# Board.net
KiCad netlist of a schematic drawn in EAGLE
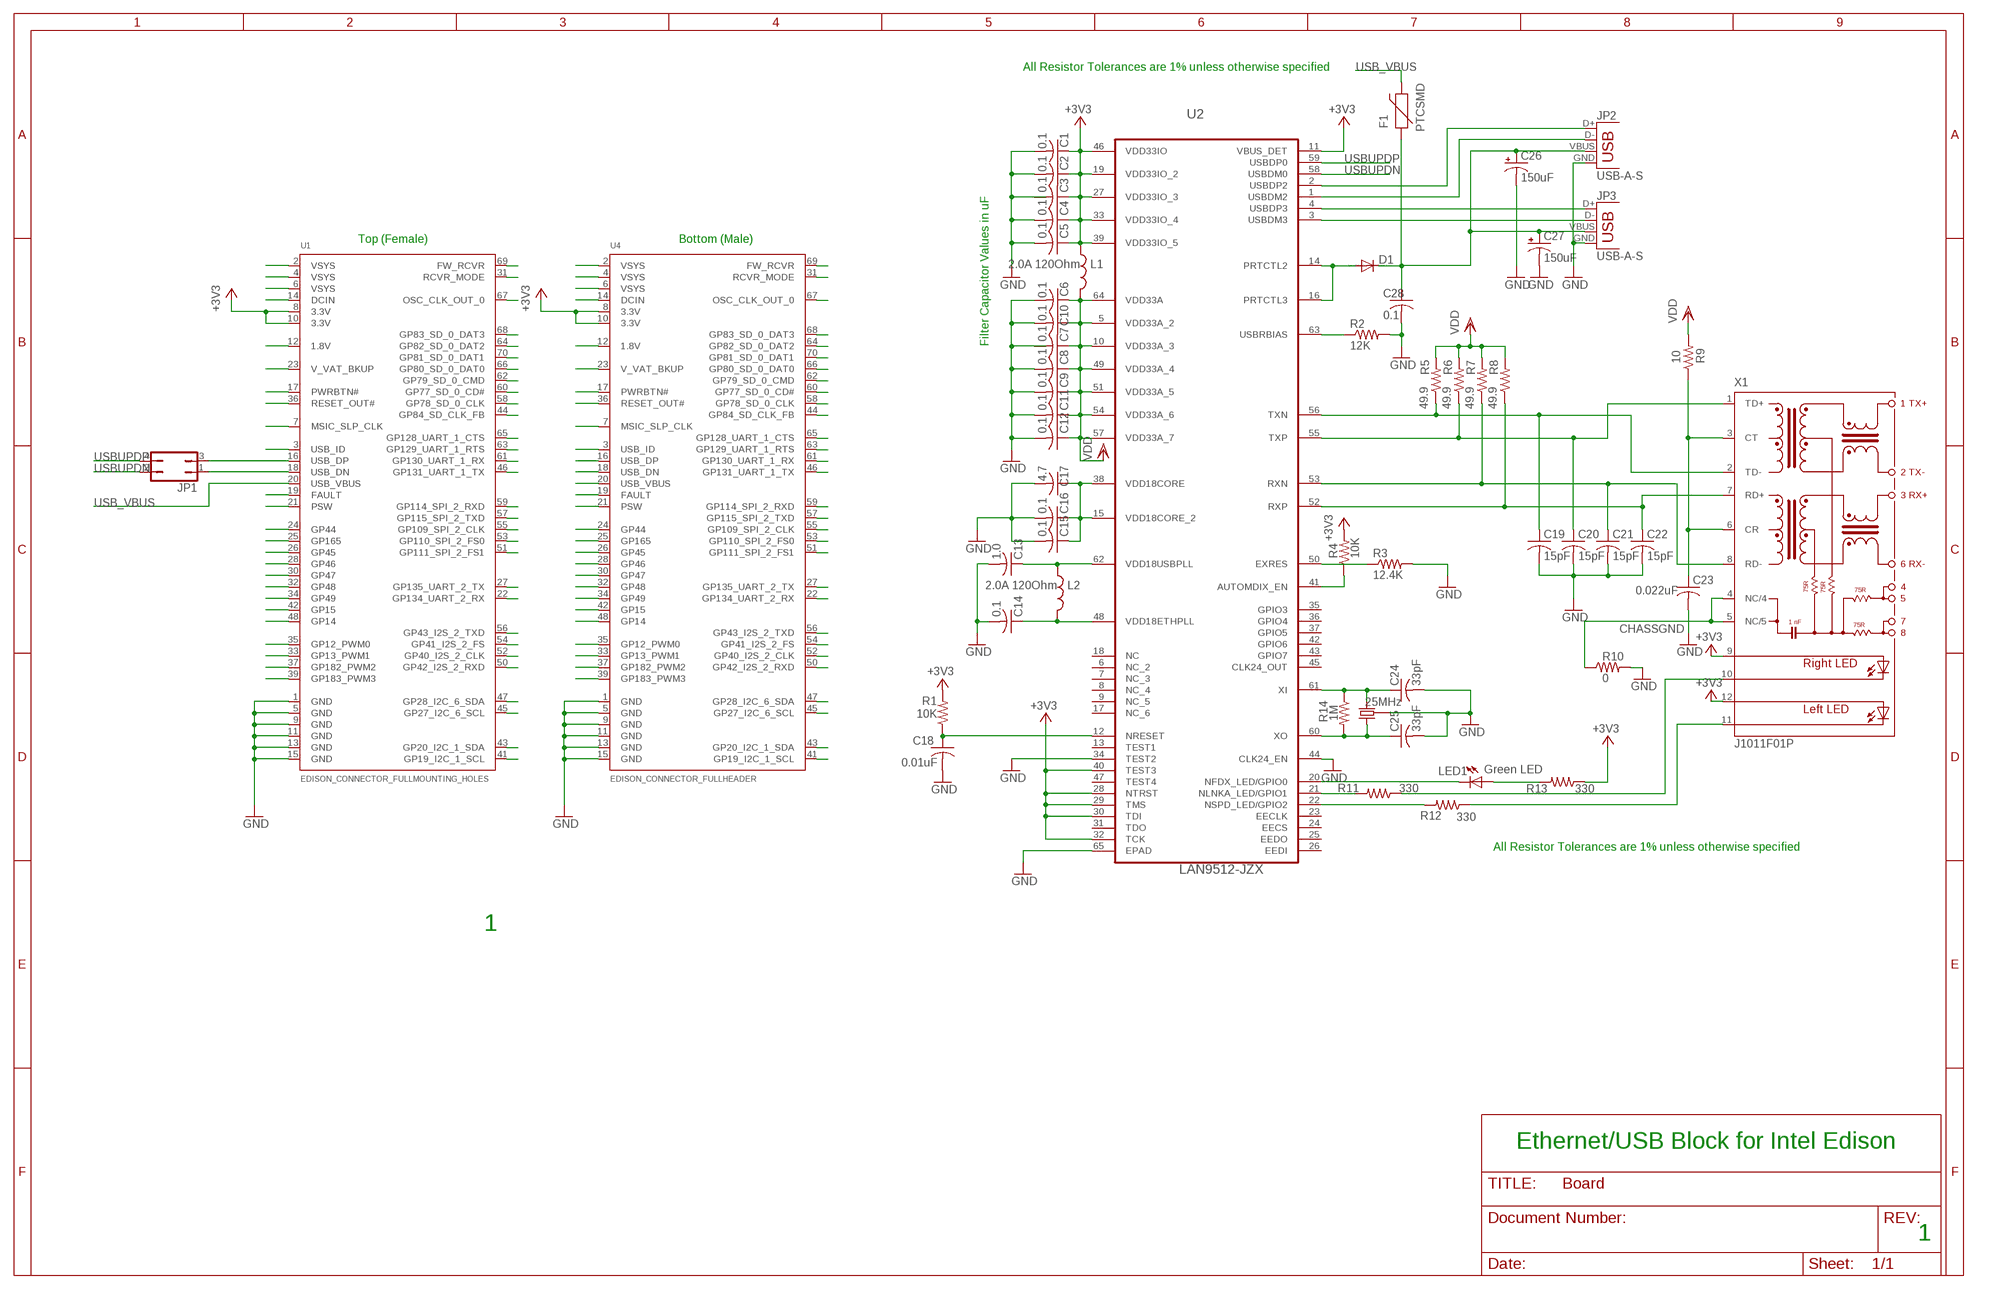
[diagram p0: schematic, sheet 1]

(export (version "E")
  (design (tool "Eeschema 10.0.6"))
  (components
    (comp (ref "C1")
      (value "0.1")
      (footprint "eagle-import:C0402K")
      (libsource (lib "eagle-import") (part "C-USC0402K"))
    )
    (comp (ref "C2")
      (value "0.1")
      (footprint "eagle-import:C0402K")
      (libsource (lib "eagle-import") (part "C-USC0402K"))
    )
    (comp (ref "C3")
      (value "0.1")
      (footprint "eagle-import:C0402K")
      (libsource (lib "eagle-import") (part "C-USC0402K"))
    )
    (comp (ref "C4")
      (value "0.1")
      (footprint "eagle-import:C0402K")
      (libsource (lib "eagle-import") (part "C-USC0402K"))
    )
    (comp (ref "C5")
      (value "0.1")
      (footprint "eagle-import:C0402K")
      (libsource (lib "eagle-import") (part "C-USC0402K"))
    )
    (comp (ref "C6")
      (value "0.1")
      (footprint "eagle-import:C0402K")
      (libsource (lib "eagle-import") (part "C-USC0402K"))
    )
    (comp (ref "C7")
      (value "0.1")
      (footprint "eagle-import:C0402K")
      (libsource (lib "eagle-import") (part "C-USC0402K"))
    )
    (comp (ref "C8")
      (value "0.1")
      (footprint "eagle-import:C0402K")
      (libsource (lib "eagle-import") (part "C-USC0402K"))
    )
    (comp (ref "C9")
      (value "0.1")
      (footprint "eagle-import:C0402K")
      (libsource (lib "eagle-import") (part "C-USC0402K"))
    )
    (comp (ref "C10")
      (value "0.1")
      (footprint "eagle-import:C0402K")
      (libsource (lib "eagle-import") (part "C-USC0402K"))
    )
    (comp (ref "C11")
      (value "0.1")
      (footprint "eagle-import:C0402K")
      (libsource (lib "eagle-import") (part "C-USC0402K"))
    )
    (comp (ref "C12")
      (value "0.1")
      (footprint "eagle-import:C0402K")
      (libsource (lib "eagle-import") (part "C-USC0402K"))
    )
    (comp (ref "C13")
      (value "1.0")
      (footprint "eagle-import:C0402K")
      (libsource (lib "eagle-import") (part "C-USC0402K"))
    )
    (comp (ref "C14")
      (value "0.1")
      (footprint "eagle-import:C0402K")
      (libsource (lib "eagle-import") (part "C-USC0402K"))
    )
    (comp (ref "C15")
      (value "0.1")
      (footprint "eagle-import:C0402K")
      (libsource (lib "eagle-import") (part "C-USC0402K"))
    )
    (comp (ref "C16")
      (value "0.1")
      (footprint "eagle-import:C0402K")
      (libsource (lib "eagle-import") (part "C-USC0402K"))
    )
    (comp (ref "C17")
      (value "4.7")
      (footprint "eagle-import:C0603K")
      (libsource (lib "eagle-import") (part "C-USC0603K"))
    )
    (comp (ref "C18")
      (value "0.01uF")
      (footprint "eagle-import:C0603K")
      (libsource (lib "eagle-import") (part "C-USC0603K"))
    )
    (comp (ref "C19")
      (value "15pF")
      (footprint "eagle-import:C0402")
      (libsource (lib "eagle-import") (part "C-USC0402"))
    )
    (comp (ref "C20")
      (value "15pF")
      (footprint "eagle-import:C0402")
      (libsource (lib "eagle-import") (part "C-USC0402"))
    )
    (comp (ref "C21")
      (value "15pF")
      (footprint "eagle-import:C0402")
      (libsource (lib "eagle-import") (part "C-USC0402"))
    )
    (comp (ref "C22")
      (value "15pF")
      (footprint "eagle-import:C0402")
      (libsource (lib "eagle-import") (part "C-USC0402"))
    )
    (comp (ref "C23")
      (value "0.022uF")
      (footprint "eagle-import:C0805")
      (libsource (lib "eagle-import") (part "resistor_C-USC0805"))
    )
    (comp (ref "C24")
      (value "33pF")
      (footprint "eagle-import:C0402")
      (libsource (lib "eagle-import") (part "C-USC0402"))
    )
    (comp (ref "C25")
      (value "33pF")
      (footprint "eagle-import:C0402")
      (libsource (lib "eagle-import") (part "C-USC0402"))
    )
    (comp (ref "C26")
      (value "150uF")
      (footprint "eagle-import:PANASONIC_E")
      (libsource (lib "eagle-import") (part "CAP_POLE"))
    )
    (comp (ref "C27")
      (value "150uF")
      (footprint "eagle-import:PANASONIC_E")
      (libsource (lib "eagle-import") (part "CAP_POLE"))
    )
    (comp (ref "C28")
      (value "0.1")
      (footprint "eagle-import:C0402K")
      (libsource (lib "eagle-import") (part "C-USC0402K"))
    )
    (comp (ref "D1")
      (value "DIODE-SOD123")
      (footprint "eagle-import:SOD123")
      (libsource (lib "eagle-import") (part "DIODE-SOD123"))
    )
    (comp (ref "F1")
      (value "PTCSMD")
      (footprint "eagle-import:PTC-1206")
      (libsource (lib "eagle-import") (part "PTCSMD"))
    )
    (comp (ref "JP1")
      (value "JP2Q")
      (footprint "eagle-import:JP2Q")
      (libsource (lib "eagle-import") (part "JP2Q"))
    )
    (comp (ref "JP2")
      (value "USB-A-S")
      (footprint "eagle-import:USB-A-S")
      (libsource (lib "eagle-import") (part "USB-A-S"))
    )
    (comp (ref "JP3")
      (value "USB-A-S")
      (footprint "eagle-import:USB-A-S")
      (libsource (lib "eagle-import") (part "USB-A-S"))
    )
    (comp (ref "L1")
      (value "2.0A 120Ohm")
      (footprint "eagle-import:L0603")
      (libsource (lib "eagle-import") (part "L-US0603"))
    )
    (comp (ref "L2")
      (value "2.0A 120Ohm")
      (footprint "eagle-import:L0603")
      (libsource (lib "eagle-import") (part "L-US0603"))
    )
    (comp (ref "LED1")
      (value "Green LED")
      (footprint "eagle-import:CHIPLED_0603")
      (libsource (lib "eagle-import") (part "LEDCHIPLED_0603"))
    )
    (comp (ref "R1")
      (value "10K")
      (footprint "eagle-import:R0603")
      (libsource (lib "eagle-import") (part "R-US_R0603"))
    )
    (comp (ref "R2")
      (value "12K")
      (footprint "eagle-import:R0603")
      (libsource (lib "eagle-import") (part "R-US_R0603"))
    )
    (comp (ref "R3")
      (value "12.4K")
      (footprint "eagle-import:R0603")
      (libsource (lib "eagle-import") (part "R-US_R0603"))
    )
    (comp (ref "R4")
      (value "10K")
      (footprint "eagle-import:R0603")
      (libsource (lib "eagle-import") (part "R-US_R0603"))
    )
    (comp (ref "R5")
      (value "49.9")
      (footprint "eagle-import:R0402")
      (libsource (lib "eagle-import") (part "R-US_R0402"))
    )
    (comp (ref "R6")
      (value "49.9")
      (footprint "eagle-import:R0402")
      (libsource (lib "eagle-import") (part "R-US_R0402"))
    )
    (comp (ref "R7")
      (value "49.9")
      (footprint "eagle-import:R0402")
      (libsource (lib "eagle-import") (part "R-US_R0402"))
    )
    (comp (ref "R8")
      (value "49.9")
      (footprint "eagle-import:R0402")
      (libsource (lib "eagle-import") (part "R-US_R0402"))
    )
    (comp (ref "R9")
      (value "10")
      (footprint "eagle-import:R0402")
      (libsource (lib "eagle-import") (part "R-US_R0402"))
    )
    (comp (ref "R10")
      (value "0")
      (footprint "eagle-import:R1210")
      (libsource (lib "eagle-import") (part "R-US_R1210"))
    )
    (comp (ref "R11")
      (value "330")
      (footprint "eagle-import:R0402")
      (libsource (lib "eagle-import") (part "R-US_R0402"))
    )
    (comp (ref "R12")
      (value "330")
      (footprint "eagle-import:R0402")
      (libsource (lib "eagle-import") (part "R-US_R0402"))
    )
    (comp (ref "R13")
      (value "330")
      (footprint "eagle-import:R0402")
      (libsource (lib "eagle-import") (part "R-US_R0402"))
    )
    (comp (ref "R14")
      (value "1M")
      (footprint "eagle-import:R0402")
      (libsource (lib "eagle-import") (part "R-US_R0402"))
    )
    (comp (ref "U$1")
      (value "25MHz")
      (footprint "eagle-import:CRYSTAL-SMD-5X3")
      (libsource (lib "eagle-import") (part "CRYSTAL-GROUNDED"))
    )
    (comp (ref "U1")
      (value "EDISON_CONNECTOR_FULLMOUNTING_HOLES")
      (footprint "eagle-import:EDISON_DAUGHTER")
      (libsource (lib "eagle-import") (part "EDISON_CONNECTOR_FULLMOUNTING_HOLES"))
    )
    (comp (ref "U2")
      (value "LAN9512-JZX")
      (footprint "eagle-import:QFN50P900X900X100-65N")
      (libsource (lib "eagle-import") (part "LAN9512-JZX"))
    )
    (comp (ref "U4")
      (value "EDISON_CONNECTOR_FULLHEADER")
      (footprint "eagle-import:DF40C-70DP-0.4(51)")
      (libsource (lib "eagle-import") (part "EDISON_CONNECTOR_FULLHEADER"))
    )
    (comp (ref "X1")
      (value "J1011F01P")
      (footprint "eagle-import:J1")
      (libsource (lib "eagle-import") (part "J1011F01P"))
    )
  )
  (nets
    (net (code "1") (name "+3V3") (class "Default")
      (node (ref "C1") (pin "1") (pinfunction "1_1") (pintype "passive"))
      (node (ref "C2") (pin "1") (pinfunction "1_1") (pintype "passive"))
      (node (ref "C3") (pin "1") (pinfunction "1_1") (pintype "passive"))
      (node (ref "C4") (pin "1") (pinfunction "1_1") (pintype "passive"))
      (node (ref "C5") (pin "1") (pinfunction "1_1") (pintype "passive"))
      (node (ref "L1") (pin "1") (pinfunction "1_1") (pintype "passive"))
      (node (ref "R1") (pin "2") (pinfunction "2_2") (pintype "passive"))
      (node (ref "R13") (pin "1") (pinfunction "1_1") (pintype "passive"))
      (node (ref "R4") (pin "2") (pinfunction "2_2") (pintype "passive"))
      (node (ref "U1") (pin "10") (pinfunction "3.3V_10") (pintype "bidirectional"))
      (node (ref "U1") (pin "8") (pinfunction "3.3V_8") (pintype "bidirectional"))
      (node (ref "U2") (pin "11") (pinfunction "VBUS_DET_11") (pintype "power_in"))
      (node (ref "U2") (pin "19") (pinfunction "VDD33IO_2_19") (pintype "power_in"))
      (node (ref "U2") (pin "27") (pinfunction "VDD33IO_3_27") (pintype "power_in"))
      (node (ref "U2") (pin "28") (pinfunction "NTRST_28") (pintype "passive"))
      (node (ref "U2") (pin "29") (pinfunction "TMS_29") (pintype "passive"))
      (node (ref "U2") (pin "30") (pinfunction "TDI_30") (pintype "passive"))
      (node (ref "U2") (pin "32") (pinfunction "TCK_32") (pintype "passive"))
      (node (ref "U2") (pin "33") (pinfunction "VDD33IO_4_33") (pintype "power_in"))
      (node (ref "U2") (pin "39") (pinfunction "VDD33IO_5_39") (pintype "power_in"))
      (node (ref "U2") (pin "40") (pinfunction "TEST3_40") (pintype "passive"))
      (node (ref "U2") (pin "46") (pinfunction "VDD33IO_46") (pintype "power_in"))
      (node (ref "U4") (pin "10") (pinfunction "3.3V_10") (pintype "bidirectional"))
      (node (ref "U4") (pin "8") (pinfunction "3.3V_8") (pintype "bidirectional"))
      (node (ref "X1") (pin "12") (pinfunction "AL_12") (pintype "passive"))
      (node (ref "X1") (pin "9") (pinfunction "A-R_9") (pintype "passive"))
    )
    (net (code "2") (name "/CHASSGND") (class "Default")
      (node (ref "R10") (pin "1") (pinfunction "1_1") (pintype "passive"))
      (node (ref "X1") (pin "4") (pinfunction "NC/4_4") (pintype "input"))
      (node (ref "X1") (pin "5") (pinfunction "NC/5_5") (pintype "input"))
    )
    (net (code "3") (name "/P2") (class "Default")
      (node (ref "U1") (pin "2") (pinfunction "VSYS_2") (pintype "bidirectional"))
      (node (ref "U4") (pin "2") (pinfunction "VSYS_2") (pintype "bidirectional"))
    )
    (net (code "4") (name "/P3") (class "Default")
      (node (ref "U1") (pin "3") (pinfunction "USB_ID_3") (pintype "bidirectional"))
      (node (ref "U4") (pin "3") (pinfunction "USB_ID_3") (pintype "bidirectional"))
    )
    (net (code "5") (name "/P4") (class "Default")
      (node (ref "U1") (pin "4") (pinfunction "VSYS_4") (pintype "bidirectional"))
      (node (ref "U4") (pin "4") (pinfunction "VSYS_4") (pintype "bidirectional"))
    )
    (net (code "6") (name "/P6") (class "Default")
      (node (ref "U1") (pin "6") (pinfunction "VSYS_6") (pintype "bidirectional"))
      (node (ref "U4") (pin "6") (pinfunction "VSYS_6") (pintype "bidirectional"))
    )
    (net (code "7") (name "/P7") (class "Default")
      (node (ref "U1") (pin "7") (pinfunction "MSIC_SLP_CLK_7") (pintype "bidirectional"))
      (node (ref "U4") (pin "7") (pinfunction "MSIC_SLP_CLK_7") (pintype "bidirectional"))
    )
    (net (code "8") (name "/P12") (class "Default")
      (node (ref "U1") (pin "12") (pinfunction "1.8V_12") (pintype "bidirectional"))
      (node (ref "U4") (pin "12") (pinfunction "1.8V_12") (pintype "bidirectional"))
    )
    (net (code "9") (name "/P14") (class "Default")
      (node (ref "U1") (pin "14") (pinfunction "DCIN_14") (pintype "bidirectional"))
      (node (ref "U4") (pin "14") (pinfunction "DCIN_14") (pintype "bidirectional"))
    )
    (net (code "10") (name "/P17") (class "Default")
      (node (ref "U1") (pin "17") (pinfunction "PWRBTN#_17") (pintype "bidirectional"))
      (node (ref "U4") (pin "17") (pinfunction "PWRBTN#_17") (pintype "bidirectional"))
    )
    (net (code "11") (name "/P19") (class "Default")
      (node (ref "U1") (pin "19") (pinfunction "FAULT_19") (pintype "bidirectional"))
      (node (ref "U4") (pin "19") (pinfunction "FAULT_19") (pintype "bidirectional"))
    )
    (net (code "12") (name "/P21") (class "Default")
      (node (ref "U1") (pin "21") (pinfunction "PSW_21") (pintype "bidirectional"))
      (node (ref "U4") (pin "21") (pinfunction "PSW_21") (pintype "bidirectional"))
    )
    (net (code "13") (name "/P22") (class "Default")
      (node (ref "U1") (pin "22") (pinfunction "GP134_UART_2_RX_22") (pintype "bidirectional"))
      (node (ref "U4") (pin "22") (pinfunction "GP134_UART_2_RX_22") (pintype "bidirectional"))
    )
    (net (code "14") (name "/P23") (class "Default")
      (node (ref "U1") (pin "23") (pinfunction "V_VAT_BKUP_23") (pintype "bidirectional"))
      (node (ref "U4") (pin "23") (pinfunction "V_VAT_BKUP_23") (pintype "bidirectional"))
    )
    (net (code "15") (name "/P24") (class "Default")
      (node (ref "U1") (pin "24") (pinfunction "GP44_24") (pintype "bidirectional"))
      (node (ref "U4") (pin "24") (pinfunction "GP44_24") (pintype "bidirectional"))
    )
    (net (code "16") (name "/P25") (class "Default")
      (node (ref "U1") (pin "25") (pinfunction "GP165_25") (pintype "bidirectional"))
      (node (ref "U4") (pin "25") (pinfunction "GP165_25") (pintype "bidirectional"))
    )
    (net (code "17") (name "/P26") (class "Default")
      (node (ref "U1") (pin "26") (pinfunction "GP45_26") (pintype "bidirectional"))
      (node (ref "U4") (pin "26") (pinfunction "GP45_26") (pintype "bidirectional"))
    )
    (net (code "18") (name "/P27") (class "Default")
      (node (ref "U1") (pin "27") (pinfunction "GP135_UART_2_TX_27") (pintype "bidirectional"))
      (node (ref "U4") (pin "27") (pinfunction "GP135_UART_2_TX_27") (pintype "bidirectional"))
    )
    (net (code "19") (name "/P28") (class "Default")
      (node (ref "U1") (pin "28") (pinfunction "GP46_28") (pintype "bidirectional"))
      (node (ref "U4") (pin "28") (pinfunction "GP46_28") (pintype "bidirectional"))
    )
    (net (code "20") (name "/P30") (class "Default")
      (node (ref "U1") (pin "30") (pinfunction "GP47_30") (pintype "bidirectional"))
      (node (ref "U4") (pin "30") (pinfunction "GP47_30") (pintype "bidirectional"))
    )
    (net (code "21") (name "/P31") (class "Default")
      (node (ref "U1") (pin "31") (pinfunction "RCVR_MODE_31") (pintype "bidirectional"))
      (node (ref "U4") (pin "31") (pinfunction "RCVR_MODE_31") (pintype "bidirectional"))
    )
    (net (code "22") (name "/P32") (class "Default")
      (node (ref "U1") (pin "32") (pinfunction "GP48_32") (pintype "bidirectional"))
      (node (ref "U4") (pin "32") (pinfunction "GP48_32") (pintype "bidirectional"))
    )
    (net (code "23") (name "/P33") (class "Default")
      (node (ref "U1") (pin "33") (pinfunction "GP13_PWM1_33") (pintype "bidirectional"))
      (node (ref "U4") (pin "33") (pinfunction "GP13_PWM1_33") (pintype "bidirectional"))
    )
    (net (code "24") (name "/P34") (class "Default")
      (node (ref "U1") (pin "34") (pinfunction "GP49_34") (pintype "bidirectional"))
      (node (ref "U4") (pin "34") (pinfunction "GP49_34") (pintype "bidirectional"))
    )
    (net (code "25") (name "/P35") (class "Default")
      (node (ref "U1") (pin "35") (pinfunction "GP12_PWM0_35") (pintype "bidirectional"))
      (node (ref "U4") (pin "35") (pinfunction "GP12_PWM0_35") (pintype "bidirectional"))
    )
    (net (code "26") (name "/P36") (class "Default")
      (node (ref "U1") (pin "36") (pinfunction "RESET_OUT#_36") (pintype "bidirectional"))
      (node (ref "U4") (pin "36") (pinfunction "RESET_OUT#_36") (pintype "bidirectional"))
    )
    (net (code "27") (name "/P37") (class "Default")
      (node (ref "U1") (pin "37") (pinfunction "GP182_PWM2_37") (pintype "bidirectional"))
      (node (ref "U4") (pin "37") (pinfunction "GP182_PWM2_37") (pintype "bidirectional"))
    )
    (net (code "28") (name "/P39") (class "Default")
      (node (ref "U1") (pin "39") (pinfunction "GP183_PWM3_39") (pintype "bidirectional"))
      (node (ref "U4") (pin "39") (pinfunction "GP183_PWM3_39") (pintype "bidirectional"))
    )
    (net (code "29") (name "/P41") (class "Default")
      (node (ref "U1") (pin "41") (pinfunction "GP19_I2C_1_SCL_41") (pintype "bidirectional"))
      (node (ref "U4") (pin "41") (pinfunction "GP19_I2C_1_SCL_41") (pintype "bidirectional"))
    )
    (net (code "30") (name "/P42") (class "Default")
      (node (ref "U1") (pin "42") (pinfunction "GP15_42") (pintype "bidirectional"))
      (node (ref "U4") (pin "42") (pinfunction "GP15_42") (pintype "bidirectional"))
    )
    (net (code "31") (name "/P43") (class "Default")
      (node (ref "U1") (pin "43") (pinfunction "GP20_I2C_1_SDA_43") (pintype "bidirectional"))
      (node (ref "U4") (pin "43") (pinfunction "GP20_I2C_1_SDA_43") (pintype "bidirectional"))
    )
    (net (code "32") (name "/P44") (class "Default")
      (node (ref "U1") (pin "44") (pinfunction "GP84_SD_CLK_FB_44") (pintype "bidirectional"))
      (node (ref "U4") (pin "44") (pinfunction "GP84_SD_CLK_FB_44") (pintype "bidirectional"))
    )
    (net (code "33") (name "/P45") (class "Default")
      (node (ref "U1") (pin "45") (pinfunction "GP27_I2C_6_SCL_45") (pintype "bidirectional"))
      (node (ref "U4") (pin "45") (pinfunction "GP27_I2C_6_SCL_45") (pintype "bidirectional"))
    )
    (net (code "34") (name "/P46") (class "Default")
      (node (ref "U1") (pin "46") (pinfunction "GP131_UART_1_TX_46") (pintype "bidirectional"))
      (node (ref "U4") (pin "46") (pinfunction "GP131_UART_1_TX_46") (pintype "bidirectional"))
    )
    (net (code "35") (name "/P47") (class "Default")
      (node (ref "U1") (pin "47") (pinfunction "GP28_I2C_6_SDA_47") (pintype "bidirectional"))
      (node (ref "U4") (pin "47") (pinfunction "GP28_I2C_6_SDA_47") (pintype "bidirectional"))
    )
    (net (code "36") (name "/P48") (class "Default")
      (node (ref "U1") (pin "48") (pinfunction "GP14_48") (pintype "bidirectional"))
      (node (ref "U4") (pin "48") (pinfunction "GP14_48") (pintype "bidirectional"))
    )
    (net (code "37") (name "/P50") (class "Default")
      (node (ref "U1") (pin "50") (pinfunction "GP42_I2S_2_RXD_50") (pintype "bidirectional"))
      (node (ref "U4") (pin "50") (pinfunction "GP42_I2S_2_RXD_50") (pintype "bidirectional"))
    )
    (net (code "38") (name "/P51") (class "Default")
      (node (ref "U1") (pin "51") (pinfunction "GP111_SPI_2_FS1_51") (pintype "bidirectional"))
      (node (ref "U4") (pin "51") (pinfunction "GP111_SPI_2_FS1_51") (pintype "bidirectional"))
    )
    (net (code "39") (name "/P52") (class "Default")
      (node (ref "U1") (pin "52") (pinfunction "GP40_I2S_2_CLK_52") (pintype "bidirectional"))
      (node (ref "U4") (pin "52") (pinfunction "GP40_I2S_2_CLK_52") (pintype "bidirectional"))
    )
    (net (code "40") (name "/P53") (class "Default")
      (node (ref "U1") (pin "53") (pinfunction "GP110_SPI_2_FS0_53") (pintype "bidirectional"))
      (node (ref "U4") (pin "53") (pinfunction "GP110_SPI_2_FS0_53") (pintype "bidirectional"))
    )
    (net (code "41") (name "/P54") (class "Default")
      (node (ref "U1") (pin "54") (pinfunction "GP41_I2S_2_FS_54") (pintype "bidirectional"))
      (node (ref "U4") (pin "54") (pinfunction "GP41_I2S_2_FS_54") (pintype "bidirectional"))
    )
    (net (code "42") (name "/P55") (class "Default")
      (node (ref "U1") (pin "55") (pinfunction "GP109_SPI_2_CLK_55") (pintype "bidirectional"))
      (node (ref "U4") (pin "55") (pinfunction "GP109_SPI_2_CLK_55") (pintype "bidirectional"))
    )
    (net (code "43") (name "/P56") (class "Default")
      (node (ref "U1") (pin "56") (pinfunction "GP43_I2S_2_TXD_56") (pintype "bidirectional"))
      (node (ref "U4") (pin "56") (pinfunction "GP43_I2S_2_TXD_56") (pintype "bidirectional"))
    )
    (net (code "44") (name "/P57") (class "Default")
      (node (ref "U1") (pin "57") (pinfunction "GP115_SPI_2_TXD_57") (pintype "bidirectional"))
      (node (ref "U4") (pin "57") (pinfunction "GP115_SPI_2_TXD_57") (pintype "bidirectional"))
    )
    (net (code "45") (name "/P58") (class "Default")
      (node (ref "U1") (pin "58") (pinfunction "GP78_SD_0_CLK_58") (pintype "bidirectional"))
      (node (ref "U4") (pin "58") (pinfunction "GP78_SD_0_CLK_58") (pintype "bidirectional"))
    )
    (net (code "46") (name "/P59") (class "Default")
      (node (ref "U1") (pin "59") (pinfunction "GP114_SPI_2_RXD_59") (pintype "bidirectional"))
      (node (ref "U4") (pin "59") (pinfunction "GP114_SPI_2_RXD_59") (pintype "bidirectional"))
    )
    (net (code "47") (name "/P60") (class "Default")
      (node (ref "U1") (pin "60") (pinfunction "GP77_SD_0_CD#_60") (pintype "bidirectional"))
      (node (ref "U4") (pin "60") (pinfunction "GP77_SD_0_CD#_60") (pintype "bidirectional"))
    )
    (net (code "48") (name "/P61") (class "Default")
      (node (ref "U1") (pin "61") (pinfunction "GP130_UART_1_RX_61") (pintype "bidirectional"))
      (node (ref "U4") (pin "61") (pinfunction "GP130_UART_1_RX_61") (pintype "bidirectional"))
    )
    (net (code "49") (name "/P62") (class "Default")
      (node (ref "U1") (pin "62") (pinfunction "GP79_SD_0_CMD_62") (pintype "bidirectional"))
      (node (ref "U4") (pin "62") (pinfunction "GP79_SD_0_CMD_62") (pintype "bidirectional"))
    )
    (net (code "50") (name "/P63") (class "Default")
      (node (ref "U1") (pin "63") (pinfunction "GP129_UART_1_RTS_63") (pintype "bidirectional"))
      (node (ref "U4") (pin "63") (pinfunction "GP129_UART_1_RTS_63") (pintype "bidirectional"))
    )
    (net (code "51") (name "/P64") (class "Default")
      (node (ref "U1") (pin "64") (pinfunction "GP82_SD_0_DAT2_64") (pintype "bidirectional"))
      (node (ref "U4") (pin "64") (pinfunction "GP82_SD_0_DAT2_64") (pintype "bidirectional"))
    )
    (net (code "52") (name "/P65") (class "Default")
      (node (ref "U1") (pin "65") (pinfunction "GP128_UART_1_CTS_65") (pintype "bidirectional"))
      (node (ref "U4") (pin "65") (pinfunction "GP128_UART_1_CTS_65") (pintype "bidirectional"))
    )
    (net (code "53") (name "/P66") (class "Default")
      (node (ref "U1") (pin "66") (pinfunction "GP80_SD_0_DAT0_66") (pintype "bidirectional"))
      (node (ref "U4") (pin "66") (pinfunction "GP80_SD_0_DAT0_66") (pintype "bidirectional"))
    )
    (net (code "54") (name "/P67") (class "Default")
      (node (ref "U1") (pin "67") (pinfunction "OSC_CLK_OUT_0_67") (pintype "bidirectional"))
      (node (ref "U4") (pin "67") (pinfunction "OSC_CLK_OUT_0_67") (pintype "bidirectional"))
    )
    (net (code "55") (name "/P68") (class "Default")
      (node (ref "U1") (pin "68") (pinfunction "GP83_SD_0_DAT3_68") (pintype "bidirectional"))
      (node (ref "U4") (pin "68") (pinfunction "GP83_SD_0_DAT3_68") (pintype "bidirectional"))
    )
    (net (code "56") (name "/P69") (class "Default")
      (node (ref "U1") (pin "69") (pinfunction "FW_RCVR_69") (pintype "bidirectional"))
      (node (ref "U4") (pin "69") (pinfunction "FW_RCVR_69") (pintype "bidirectional"))
    )
    (net (code "57") (name "/P70") (class "Default")
      (node (ref "U1") (pin "70") (pinfunction "GP81_SD_0_DAT1_70") (pintype "bidirectional"))
      (node (ref "U4") (pin "70") (pinfunction "GP81_SD_0_DAT1_70") (pintype "bidirectional"))
    )
    (net (code "58") (name "/USBUP") (class "Default")
      (node (ref "JP1") (pin "3") (pinfunction "3_3") (pintype "passive"))
      (node (ref "U1") (pin "16") (pinfunction "USB_DP_16") (pintype "bidirectional"))
      (node (ref "U4") (pin "16") (pinfunction "USB_DP_16") (pintype "bidirectional"))
    )
    (net (code "59") (name "/USBUP2") (class "Default")
      (node (ref "JP1") (pin "1") (pinfunction "1_1") (pintype "passive"))
      (node (ref "U1") (pin "18") (pinfunction "USB_DN_18") (pintype "bidirectional"))
      (node (ref "U4") (pin "18") (pinfunction "USB_DN_18") (pintype "bidirectional"))
    )
    (net (code "60") (name "/USBUPDN") (class "Default")
      (node (ref "JP1") (pin "2") (pinfunction "2_2") (pintype "passive"))
      (node (ref "U2") (pin "58") (pinfunction "USBDM0_58") (pintype "passive"))
    )
    (net (code "61") (name "/USBUPDP") (class "Default")
      (node (ref "JP1") (pin "4") (pinfunction "4_4") (pintype "passive"))
      (node (ref "U2") (pin "59") (pinfunction "USBDP0_59") (pintype "passive"))
    )
    (net (code "62") (name "/USB_VBUS") (class "Default")
      (node (ref "F1") (pin "2") (pinfunction "2_2") (pintype "bidirectional"))
      (node (ref "U1") (pin "20") (pinfunction "USB_VBUS_20") (pintype "bidirectional"))
      (node (ref "U4") (pin "20") (pinfunction "USB_VBUS_20") (pintype "bidirectional"))
    )
    (net (code "63") (name "GND") (class "Default")
      (node (ref "C1") (pin "2") (pinfunction "2_2") (pintype "passive"))
      (node (ref "C10") (pin "2") (pinfunction "2_2") (pintype "passive"))
      (node (ref "C11") (pin "2") (pinfunction "2_2") (pintype "passive"))
      (node (ref "C12") (pin "2") (pinfunction "2_2") (pintype "passive"))
      (node (ref "C13") (pin "2") (pinfunction "2_2") (pintype "passive"))
      (node (ref "C14") (pin "2") (pinfunction "2_2") (pintype "passive"))
      (node (ref "C15") (pin "2") (pinfunction "2_2") (pintype "passive"))
      (node (ref "C16") (pin "2") (pinfunction "2_2") (pintype "passive"))
      (node (ref "C17") (pin "2") (pinfunction "2_2") (pintype "passive"))
      (node (ref "C18") (pin "2") (pinfunction "2_2") (pintype "passive"))
      (node (ref "C19") (pin "2") (pinfunction "2_2") (pintype "passive"))
      (node (ref "C2") (pin "2") (pinfunction "2_2") (pintype "passive"))
      (node (ref "C20") (pin "2") (pinfunction "2_2") (pintype "passive"))
      (node (ref "C21") (pin "2") (pinfunction "2_2") (pintype "passive"))
      (node (ref "C22") (pin "2") (pinfunction "2_2") (pintype "passive"))
      (node (ref "C23") (pin "2") (pinfunction "2_2") (pintype "passive"))
      (node (ref "C24") (pin "2") (pinfunction "2_2") (pintype "passive"))
      (node (ref "C25") (pin "2") (pinfunction "2_2") (pintype "passive"))
      (node (ref "C26") (pin "-") (pinfunction "-_-") (pintype "passive"))
      (node (ref "C27") (pin "-") (pinfunction "-_-") (pintype "passive"))
      (node (ref "C28") (pin "2") (pinfunction "2_2") (pintype "passive"))
      (node (ref "C3") (pin "2") (pinfunction "2_2") (pintype "passive"))
      (node (ref "C4") (pin "2") (pinfunction "2_2") (pintype "passive"))
      (node (ref "C5") (pin "2") (pinfunction "2_2") (pintype "passive"))
      (node (ref "C6") (pin "2") (pinfunction "2_2") (pintype "passive"))
      (node (ref "C7") (pin "2") (pinfunction "2_2") (pintype "passive"))
      (node (ref "C8") (pin "2") (pinfunction "2_2") (pintype "passive"))
      (node (ref "C9") (pin "2") (pinfunction "2_2") (pintype "passive"))
      (node (ref "JP2") (pin "GND") (pinfunction "GND_GND") (pintype "bidirectional"))
      (node (ref "JP3") (pin "GND") (pinfunction "GND_GND") (pintype "bidirectional"))
      (node (ref "R10") (pin "2") (pinfunction "2_2") (pintype "passive"))
      (node (ref "R2") (pin "2") (pinfunction "2_2") (pintype "passive"))
      (node (ref "R3") (pin "2") (pinfunction "2_2") (pintype "passive"))
      (node (ref "U$1") (pin "2") (pinfunction "3_2") (pintype "passive"))
      (node (ref "U$1") (pin "4") (pinfunction "3_4") (pintype "passive"))
      (node (ref "U1") (pin "1") (pinfunction "GND_1") (pintype "bidirectional"))
      (node (ref "U1") (pin "11") (pinfunction "GND_11") (pintype "bidirectional"))
      (node (ref "U1") (pin "13") (pinfunction "GND_13") (pintype "bidirectional"))
      (node (ref "U1") (pin "15") (pinfunction "GND_15") (pintype "bidirectional"))
      (node (ref "U1") (pin "5") (pinfunction "GND_5") (pintype "bidirectional"))
      (node (ref "U1") (pin "9") (pinfunction "GND_9") (pintype "bidirectional"))
      (node (ref "U2") (pin "34") (pinfunction "TEST2_34") (pintype "passive"))
      (node (ref "U2") (pin "44") (pinfunction "CLK24_EN_44") (pintype "passive"))
      (node (ref "U2") (pin "65") (pinfunction "EPAD_65") (pintype "passive"))
      (node (ref "U4") (pin "1") (pinfunction "GND_1") (pintype "bidirectional"))
      (node (ref "U4") (pin "11") (pinfunction "GND_11") (pintype "bidirectional"))
      (node (ref "U4") (pin "13") (pinfunction "GND_13") (pintype "bidirectional"))
      (node (ref "U4") (pin "15") (pinfunction "GND_15") (pintype "bidirectional"))
      (node (ref "U4") (pin "5") (pinfunction "GND_5") (pintype "bidirectional"))
      (node (ref "U4") (pin "9") (pinfunction "GND_9") (pintype "bidirectional"))
    )
    (net (code "64") (name "Net-(C26-Pad+)") (class "Default")
      (node (ref "C26") (pin "+") (pinfunction "+_+") (pintype "passive"))
      (node (ref "C27") (pin "+") (pinfunction "+_+") (pintype "passive"))
      (node (ref "C28") (pin "1") (pinfunction "1_1") (pintype "passive"))
      (node (ref "D1") (pin "C") (pinfunction "C_C") (pintype "passive"))
      (node (ref "F1") (pin "1") (pinfunction "1_1") (pintype "bidirectional"))
      (node (ref "JP2") (pin "VBUS") (pinfunction "VBUS_VBUS") (pintype "bidirectional"))
      (node (ref "JP3") (pin "VBUS") (pinfunction "VBUS_VBUS") (pintype "bidirectional"))
    )
    (net (code "65") (name "Net-(LED1-PadA)") (class "Default")
      (node (ref "LED1") (pin "A") (pinfunction "A_A") (pintype "passive"))
      (node (ref "R13") (pin "2") (pinfunction "2_2") (pintype "passive"))
    )
    (net (code "66") (name "Net-(U$1-1)") (class "Default")
      (node (ref "C25") (pin "1") (pinfunction "1_1") (pintype "passive"))
      (node (ref "R14") (pin "2") (pinfunction "2_2") (pintype "passive"))
      (node (ref "U$1") (pin "3") (pinfunction "1_3") (pintype "passive"))
      (node (ref "U2") (pin "60") (pinfunction "XO_60") (pintype "passive"))
    )
    (net (code "67") (name "Net-(U$1-2)") (class "Default")
      (node (ref "C24") (pin "1") (pinfunction "1_1") (pintype "passive"))
      (node (ref "R14") (pin "1") (pinfunction "1_1") (pintype "passive"))
      (node (ref "U$1") (pin "1") (pinfunction "2_1") (pintype "passive"))
      (node (ref "U2") (pin "61") (pinfunction "XI_61") (pintype "passive"))
    )
    (net (code "68") (name "Net-(U2-AUTOMDIX_EN)") (class "Default")
      (node (ref "R4") (pin "1") (pinfunction "1_1") (pintype "passive"))
      (node (ref "U2") (pin "41") (pinfunction "AUTOMDIX_EN_41") (pintype "passive"))
    )
    (net (code "69") (name "Net-(U2-EXRES)") (class "Default")
      (node (ref "R3") (pin "1") (pinfunction "1_1") (pintype "passive"))
      (node (ref "U2") (pin "50") (pinfunction "EXRES_50") (pintype "passive"))
    )
    (net (code "70") (name "Net-(U2-NFDX_LED{slash}GPIO0)") (class "Default")
      (node (ref "LED1") (pin "C") (pinfunction "C_C") (pintype "passive"))
      (node (ref "U2") (pin "20") (pinfunction "NFDX_LED/GPIO0_20") (pintype "bidirectional"))
    )
    (net (code "71") (name "Net-(U2-NLNKA_LED{slash}GPIO1)") (class "Default")
      (node (ref "R11") (pin "2") (pinfunction "2_2") (pintype "passive"))
      (node (ref "U2") (pin "21") (pinfunction "NLNKA_LED/GPIO1_21") (pintype "bidirectional"))
    )
    (net (code "72") (name "Net-(U2-NRESET)") (class "Default")
      (node (ref "C18") (pin "1") (pinfunction "1_1") (pintype "passive"))
      (node (ref "R1") (pin "1") (pinfunction "1_1") (pintype "passive"))
      (node (ref "U2") (pin "12") (pinfunction "NRESET_12") (pintype "passive"))
    )
    (net (code "73") (name "Net-(U2-NSPD_LED{slash}GPIO2)") (class "Default")
      (node (ref "R12") (pin "2") (pinfunction "2_2") (pintype "passive"))
      (node (ref "U2") (pin "22") (pinfunction "NSPD_LED/GPIO2_22") (pintype "bidirectional"))
    )
    (net (code "74") (name "Net-(U2-PRTCTL2)") (class "Default")
      (node (ref "D1") (pin "A") (pinfunction "A_A") (pintype "passive"))
      (node (ref "U2") (pin "14") (pinfunction "PRTCTL2_14") (pintype "passive"))
      (node (ref "U2") (pin "16") (pinfunction "PRTCTL3_16") (pintype "passive"))
    )
    (net (code "75") (name "Net-(U2-RXN)") (class "Default")
      (node (ref "C21") (pin "1") (pinfunction "1_1") (pintype "passive"))
      (node (ref "R7") (pin "1") (pinfunction "1_1") (pintype "passive"))
      (node (ref "U2") (pin "53") (pinfunction "RXN_53") (pintype "passive"))
      (node (ref "X1") (pin "8") (pinfunction "RD-_8") (pintype "input"))
    )
    (net (code "76") (name "Net-(U2-RXP)") (class "Default")
      (node (ref "C22") (pin "1") (pinfunction "1_1") (pintype "passive"))
      (node (ref "R8") (pin "1") (pinfunction "1_1") (pintype "passive"))
      (node (ref "U2") (pin "52") (pinfunction "RXP_52") (pintype "passive"))
      (node (ref "X1") (pin "7") (pinfunction "RD+_7") (pintype "input"))
    )
    (net (code "77") (name "Net-(U2-TXN)") (class "Default")
      (node (ref "C19") (pin "1") (pinfunction "1_1") (pintype "passive"))
      (node (ref "R5") (pin "1") (pinfunction "1_1") (pintype "passive"))
      (node (ref "U2") (pin "56") (pinfunction "TXN_56") (pintype "passive"))
      (node (ref "X1") (pin "2") (pinfunction "TD-_2") (pintype "input"))
    )
    (net (code "78") (name "Net-(U2-TXP)") (class "Default")
      (node (ref "C20") (pin "1") (pinfunction "1_1") (pintype "passive"))
      (node (ref "R6") (pin "1") (pinfunction "1_1") (pintype "passive"))
      (node (ref "U2") (pin "55") (pinfunction "TXP_55") (pintype "passive"))
      (node (ref "X1") (pin "1") (pinfunction "TD+_1") (pintype "input"))
    )
    (net (code "79") (name "Net-(U2-USBDM2)") (class "Default")
      (node (ref "JP2") (pin "D-") (pinfunction "D-_D-") (pintype "bidirectional"))
      (node (ref "U2") (pin "1") (pinfunction "USBDM2_1") (pintype "passive"))
    )
    (net (code "80") (name "Net-(U2-USBDM3)") (class "Default")
      (node (ref "JP3") (pin "D-") (pinfunction "D-_D-") (pintype "bidirectional"))
      (node (ref "U2") (pin "3") (pinfunction "USBDM3_3") (pintype "passive"))
    )
    (net (code "81") (name "Net-(U2-USBDP2)") (class "Default")
      (node (ref "JP2") (pin "D+") (pinfunction "D+_D+") (pintype "bidirectional"))
      (node (ref "U2") (pin "2") (pinfunction "USBDP2_2") (pintype "passive"))
    )
    (net (code "82") (name "Net-(U2-USBDP3)") (class "Default")
      (node (ref "JP3") (pin "D+") (pinfunction "D+_D+") (pintype "bidirectional"))
      (node (ref "U2") (pin "4") (pinfunction "USBDP3_4") (pintype "passive"))
    )
    (net (code "83") (name "Net-(U2-USBRBIAS)") (class "Default")
      (node (ref "R2") (pin "1") (pinfunction "1_1") (pintype "passive"))
      (node (ref "U2") (pin "63") (pinfunction "USBRBIAS_63") (pintype "passive"))
    )
    (net (code "84") (name "Net-(U2-VDD18CORE)") (class "Default")
      (node (ref "C15") (pin "1") (pinfunction "1_1") (pintype "passive"))
      (node (ref "C16") (pin "1") (pinfunction "1_1") (pintype "passive"))
      (node (ref "C17") (pin "1") (pinfunction "1_1") (pintype "passive"))
      (node (ref "U2") (pin "15") (pinfunction "VDD18CORE_2_15") (pintype "power_in"))
      (node (ref "U2") (pin "38") (pinfunction "VDD18CORE_38") (pintype "power_in"))
    )
    (net (code "85") (name "Net-(U2-VDD18ETHPLL)") (class "Default")
      (node (ref "C14") (pin "1") (pinfunction "1_1") (pintype "passive"))
      (node (ref "L2") (pin "2") (pinfunction "2_2") (pintype "passive"))
      (node (ref "U2") (pin "48") (pinfunction "VDD18ETHPLL_48") (pintype "power_in"))
    )
    (net (code "86") (name "Net-(U2-VDD18USBPLL)") (class "Default")
      (node (ref "C13") (pin "1") (pinfunction "1_1") (pintype "passive"))
      (node (ref "L2") (pin "1") (pinfunction "1_1") (pintype "passive"))
      (node (ref "U2") (pin "62") (pinfunction "VDD18USBPLL_62") (pintype "power_in"))
    )
    (net (code "87") (name "Net-(X1-C-L)") (class "Default")
      (node (ref "R12") (pin "1") (pinfunction "1_1") (pintype "passive"))
      (node (ref "X1") (pin "11") (pinfunction "C-L_11") (pintype "passive"))
    )
    (net (code "88") (name "Net-(X1-C-R)") (class "Default")
      (node (ref "R11") (pin "1") (pinfunction "1_1") (pintype "passive"))
      (node (ref "X1") (pin "10") (pinfunction "C-R_10") (pintype "passive"))
    )
    (net (code "89") (name "Net-(X1-CR)") (class "Default")
      (node (ref "C23") (pin "1") (pinfunction "1_1") (pintype "passive"))
      (node (ref "R9") (pin "1") (pinfunction "1_1") (pintype "passive"))
      (node (ref "X1") (pin "3") (pinfunction "CT_3") (pintype "input"))
      (node (ref "X1") (pin "6") (pinfunction "CR_6") (pintype "input"))
    )
    (net (code "90") (name "VDD") (class "Default")
      (node (ref "C10") (pin "1") (pinfunction "1_1") (pintype "passive"))
      (node (ref "C11") (pin "1") (pinfunction "1_1") (pintype "passive"))
      (node (ref "C12") (pin "1") (pinfunction "1_1") (pintype "passive"))
      (node (ref "C6") (pin "1") (pinfunction "1_1") (pintype "passive"))
      (node (ref "C7") (pin "1") (pinfunction "1_1") (pintype "passive"))
      (node (ref "C8") (pin "1") (pinfunction "1_1") (pintype "passive"))
      (node (ref "C9") (pin "1") (pinfunction "1_1") (pintype "passive"))
      (node (ref "L1") (pin "2") (pinfunction "2_2") (pintype "passive"))
      (node (ref "R5") (pin "2") (pinfunction "2_2") (pintype "passive"))
      (node (ref "R6") (pin "2") (pinfunction "2_2") (pintype "passive"))
      (node (ref "R7") (pin "2") (pinfunction "2_2") (pintype "passive"))
      (node (ref "R8") (pin "2") (pinfunction "2_2") (pintype "passive"))
      (node (ref "R9") (pin "2") (pinfunction "2_2") (pintype "passive"))
      (node (ref "U2") (pin "10") (pinfunction "VDD33A_3_10") (pintype "power_in"))
      (node (ref "U2") (pin "49") (pinfunction "VDD33A_4_49") (pintype "power_in"))
      (node (ref "U2") (pin "5") (pinfunction "VDD33A_2_5") (pintype "power_in"))
      (node (ref "U2") (pin "51") (pinfunction "VDD33A_5_51") (pintype "power_in"))
      (node (ref "U2") (pin "54") (pinfunction "VDD33A_6_54") (pintype "power_in"))
      (node (ref "U2") (pin "57") (pinfunction "VDD33A_7_57") (pintype "power_in"))
      (node (ref "U2") (pin "64") (pinfunction "VDD33A_64") (pintype "power_in"))
    )
    (net (code "91") (name "unconnected-(U2-CLK24_OUT-Pad45)") (class "Default")
      (node (ref "U2") (pin "45") (pinfunction "CLK24_OUT_45") (pintype "passive"))
    )
    (net (code "92") (name "unconnected-(U2-EECLK-Pad23)") (class "Default")
      (node (ref "U2") (pin "23") (pinfunction "EECLK_23") (pintype "passive"))
    )
    (net (code "93") (name "unconnected-(U2-EECS-Pad24)") (class "Default")
      (node (ref "U2") (pin "24") (pinfunction "EECS_24") (pintype "passive"))
    )
    (net (code "94") (name "unconnected-(U2-EEDI-Pad26)") (class "Default")
      (node (ref "U2") (pin "26") (pinfunction "EEDI_26") (pintype "passive"))
    )
    (net (code "95") (name "unconnected-(U2-EEDO-Pad25)") (class "Default")
      (node (ref "U2") (pin "25") (pinfunction "EEDO_25") (pintype "passive"))
    )
    (net (code "96") (name "unconnected-(U2-GPIO3-Pad35)") (class "Default")
      (node (ref "U2") (pin "35") (pinfunction "GPIO3_35") (pintype "bidirectional"))
    )
    (net (code "97") (name "unconnected-(U2-GPIO4-Pad36)") (class "Default")
      (node (ref "U2") (pin "36") (pinfunction "GPIO4_36") (pintype "bidirectional"))
    )
    (net (code "98") (name "unconnected-(U2-GPIO5-Pad37)") (class "Default")
      (node (ref "U2") (pin "37") (pinfunction "GPIO5_37") (pintype "bidirectional"))
    )
    (net (code "99") (name "unconnected-(U2-GPIO6-Pad42)") (class "Default")
      (node (ref "U2") (pin "42") (pinfunction "GPIO6_42") (pintype "bidirectional"))
    )
    (net (code "100") (name "unconnected-(U2-GPIO7-Pad43)") (class "Default")
      (node (ref "U2") (pin "43") (pinfunction "GPIO7_43") (pintype "bidirectional"))
    )
    (net (code "101") (name "unconnected-(U2-NC-Pad18)") (class "Default")
      (node (ref "U2") (pin "18") (pinfunction "NC_18") (pintype "no_connect"))
    )
    (net (code "102") (name "unconnected-(U2-NC_2-Pad6)") (class "Default")
      (node (ref "U2") (pin "6") (pinfunction "NC_2_6") (pintype "no_connect"))
    )
    (net (code "103") (name "unconnected-(U2-NC_3-Pad7)") (class "Default")
      (node (ref "U2") (pin "7") (pinfunction "NC_3_7") (pintype "no_connect"))
    )
    (net (code "104") (name "unconnected-(U2-NC_4-Pad8)") (class "Default")
      (node (ref "U2") (pin "8") (pinfunction "NC_4_8") (pintype "no_connect"))
    )
    (net (code "105") (name "unconnected-(U2-NC_5-Pad9)") (class "Default")
      (node (ref "U2") (pin "9") (pinfunction "NC_5_9") (pintype "no_connect"))
    )
    (net (code "106") (name "unconnected-(U2-NC_6-Pad17)") (class "Default")
      (node (ref "U2") (pin "17") (pinfunction "NC_6_17") (pintype "no_connect"))
    )
    (net (code "107") (name "unconnected-(U2-TDO-Pad31)") (class "Default")
      (node (ref "U2") (pin "31") (pinfunction "TDO_31") (pintype "passive"))
    )
    (net (code "108") (name "unconnected-(U2-TEST1-Pad13)") (class "Default")
      (node (ref "U2") (pin "13") (pinfunction "TEST1_13") (pintype "passive"))
    )
    (net (code "109") (name "unconnected-(U2-TEST4-Pad47)") (class "Default")
      (node (ref "U2") (pin "47") (pinfunction "TEST4_47") (pintype "passive"))
    )
  )
)
